# POWER2.net
KiCad netlist of a schematic drawn in Altium Designer
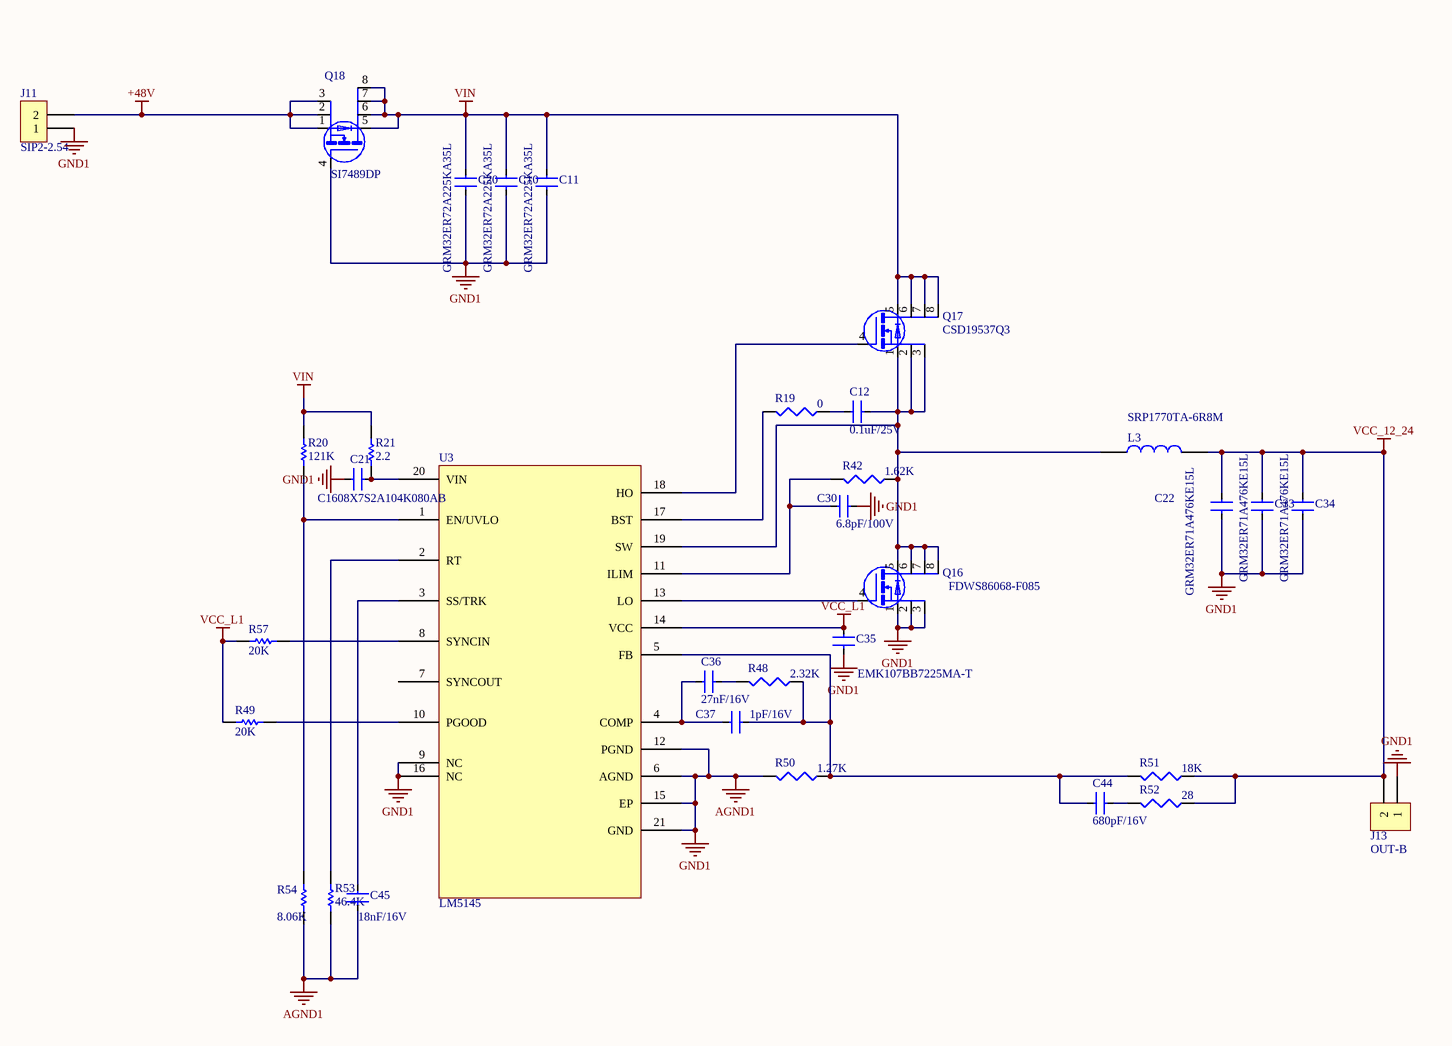
[diagram p0: POWER2.SchDoc]

(export (version "E")
  (design (tool "Eeschema 10.0.6"))
  (components
    (comp (ref "C10")
      (value "GRM32ER72A225KA35L")
      (footprint "1210C")
      (description "CCX85-103")
      (libsource (lib "无极性电容") (part "0.01UF"))
    )
    (comp (ref "C11")
      (value "GRM32ER72A225KA35L")
      (footprint "1210C")
      (description "CCX85-103")
      (libsource (lib "无极性电容") (part "0.01UF"))
    )
    (comp (ref "C12")
      (value "0.1uF/25V")
      (footprint "0603C")
      (description "CCX85-103")
      (libsource (lib "无极性电容") (part "0.01UF"))
    )
    (comp (ref "C20")
      (value "GRM32ER72A225KA35L")
      (footprint "1210C")
      (description "CCX85-103")
      (libsource (lib "无极性电容") (part "0.01UF"))
    )
    (comp (ref "C21")
      (value "C1608X7S2A104K080AB")
      (footprint "0603C")
      (description "CCX85-103")
      (libsource (lib "无极性电容") (part "0.01UF"))
    )
    (comp (ref "C22")
      (value "GRM32ER71A476KE15L")
      (footprint "1210C")
      (description "CCX85-103")
      (libsource (lib "无极性电容") (part "0.01UF"))
    )
    (comp (ref "C30")
      (value "6.8pF/100V")
      (footprint "0603C")
      (description "CCX85-103")
      (libsource (lib "无极性电容") (part "0.01UF"))
    )
    (comp (ref "C33")
      (value "GRM32ER71A476KE15L")
      (footprint "1210C")
      (description "CCX85-103")
      (libsource (lib "无极性电容") (part "0.01UF"))
    )
    (comp (ref "C34")
      (value "GRM32ER71A476KE15L")
      (footprint "1210C")
      (description "CCX85-103")
      (libsource (lib "无极性电容") (part "0.01UF"))
    )
    (comp (ref "C35")
      (value "EMK107BB7225MA-T")
      (footprint "0603C")
      (description "CCX85-103")
      (libsource (lib "无极性电容") (part "0.01UF"))
    )
    (comp (ref "C36")
      (value "27nF/16V")
      (footprint "0603C")
      (description "CCX85-103")
      (libsource (lib "无极性电容") (part "0.01UF"))
    )
    (comp (ref "C37")
      (value "1pF/16V")
      (footprint "0603C")
      (description "CCX85-103")
      (libsource (lib "无极性电容") (part "0.01UF"))
    )
    (comp (ref "C44")
      (value "680pF/16V")
      (footprint "0603C")
      (description "CCX85-103")
      (libsource (lib "无极性电容") (part "0.01UF"))
    )
    (comp (ref "C45")
      (value "18nF/16V")
      (footprint "0603C")
      (description "CCX85-103")
      (libsource (lib "无极性电容") (part "0.01UF"))
    )
    (comp (ref "J11")
      (value "SIP2-2.54")
      (footprint "CH3.96-2P")
      (description "CN-SIP2-2.54")
      (libsource (lib "接插件") (part "SIP2-2.54"))
    )
    (comp (ref "J13")
      (value "OUT-B")
      (footprint "CH3.96-2P")
      (description "Connector")
      (libsource (lib "SM") (part "CON2"))
    )
    (comp (ref "L3")
      (value "SRP1770TA-6R8M")
      (footprint "SRP1270-2R2M")
      (libsource (lib "*") (part "INDUCTOR"))
    )
    (comp (ref "Q16")
      (value "FDWS86068-F085")
      (footprint "PowerPAK SO-8")
      (description "Si4004DY")
      (libsource (lib "") (part "Si4004DY_1"))
    )
    (comp (ref "Q17")
      (value "CSD19537Q3")
      (footprint "PowerPAK SO-8")
      (description "Si4004DY")
      (libsource (lib "") (part "Si4004DY_1"))
    )
    (comp (ref "Q18")
      (value "SI7489DP")
      (footprint "PowerPAK SO-8")
      (description "Si4004DY")
      (libsource (lib "Schlib_20110825") (part "Si4004DY"))
    )
    (comp (ref "R19")
      (value "0")
      (footprint "0603R")
      (description "Resistor")
      (fields (field (name "PUBLISHER") "Altium Limited"))
      (libsource (lib "SM") (part "Res3"))
    )
    (comp (ref "R20")
      (value "121K")
      (footprint "0805R")
      (description "Semiconductor Resistor")
      (fields (field (name "PUBLISHER") "Altium Limited"))
      (libsource (lib "Miscellaneous Devices") (part "Res Semi"))
    )
    (comp (ref "R21")
      (value "2.2")
      (footprint "0603R")
      (description "Semiconductor Resistor")
      (fields (field (name "PUBLISHER") "Altium Limited"))
      (libsource (lib "Miscellaneous Devices") (part "Res Semi"))
    )
    (comp (ref "R42")
      (value "1.62K")
      (footprint "0603R")
      (description "Resistor")
      (fields (field (name "PUBLISHER") "Altium Limited"))
      (libsource (lib "SM") (part "Res3"))
    )
    (comp (ref "R48")
      (value "2.32K")
      (footprint "0603R")
      (description "Resistor")
      (fields (field (name "PUBLISHER") "Altium Limited"))
      (libsource (lib "SM") (part "Res3"))
    )
    (comp (ref "R49")
      (value "20K")
      (footprint "0603R")
      (description "Semiconductor Resistor")
      (fields (field (name "PUBLISHER") "Altium Limited"))
      (libsource (lib "Miscellaneous Devices") (part "Res Semi"))
    )
    (comp (ref "R50")
      (value "1.27K")
      (footprint "0603R")
      (description "Resistor")
      (fields (field (name "PUBLISHER") "Altium Limited"))
      (libsource (lib "SM") (part "Res3"))
    )
    (comp (ref "R51")
      (value "18K")
      (footprint "0603R")
      (description "Resistor")
      (fields (field (name "PUBLISHER") "Altium Limited"))
      (libsource (lib "SM") (part "Res3"))
    )
    (comp (ref "R52")
      (value "28")
      (footprint "0603R")
      (description "Resistor")
      (fields (field (name "PUBLISHER") "Altium Limited"))
      (libsource (lib "SM") (part "Res3"))
    )
    (comp (ref "R53")
      (value "46.4K")
      (footprint "0603R")
      (description "Semiconductor Resistor")
      (fields (field (name "PUBLISHER") "Altium Limited"))
      (libsource (lib "Miscellaneous Devices") (part "Res Semi"))
    )
    (comp (ref "R54")
      (value "8.06K")
      (footprint "0603R")
      (description "Semiconductor Resistor")
      (fields (field (name "PUBLISHER") "Altium Limited"))
      (libsource (lib "Miscellaneous Devices") (part "Res Semi"))
    )
    (comp (ref "R57")
      (value "20K")
      (footprint "0603R")
      (description "Semiconductor Resistor")
      (fields (field (name "PUBLISHER") "Altium Limited"))
      (libsource (lib "Miscellaneous Devices") (part "Res Semi"))
    )
    (comp (ref "U3")
      (value "LM5145")
      (footprint "QFN050P600-8N")
      (libsource (lib "Schlib_20110825") (part "LM5145"))
    )
  )
  (nets
    (net (code "1") (name "+48V") (class "Default")
      (node (ref "J11") (pin "2") (pinfunction "2_2") (pintype "passive"))
      (node (ref "Q18") (pin "1") (pinfunction "S_1") (pintype "passive"))
      (node (ref "Q18") (pin "2") (pinfunction "S_2") (pintype "passive"))
      (node (ref "Q18") (pin "3") (pinfunction "S_3") (pintype "passive"))
    )
    (net (code "2") (name "AGND1") (class "Default")
      (node (ref "C10") (pin "2") (pinfunction "2_2") (pintype "passive"))
      (node (ref "C11") (pin "2") (pinfunction "2_2") (pintype "passive"))
      (node (ref "C20") (pin "2") (pinfunction "2_2") (pintype "passive"))
      (node (ref "C21") (pin "1") (pinfunction "1_1") (pintype "passive"))
      (node (ref "C22") (pin "2") (pinfunction "2_2") (pintype "passive"))
      (node (ref "C30") (pin "1") (pinfunction "1_1") (pintype "passive"))
      (node (ref "C33") (pin "2") (pinfunction "2_2") (pintype "passive"))
      (node (ref "C34") (pin "2") (pinfunction "2_2") (pintype "passive"))
      (node (ref "C35") (pin "2") (pinfunction "2_2") (pintype "passive"))
      (node (ref "C45") (pin "2") (pinfunction "2_2") (pintype "passive"))
      (node (ref "J11") (pin "1") (pinfunction "1_1") (pintype "passive"))
      (node (ref "J13") (pin "1") (pinfunction "1_1") (pintype "passive"))
      (node (ref "Q16") (pin "1") (pinfunction "S_1") (pintype "passive"))
      (node (ref "Q16") (pin "2") (pinfunction "S_2") (pintype "passive"))
      (node (ref "Q16") (pin "3") (pinfunction "S_3") (pintype "passive"))
      (node (ref "Q18") (pin "4") (pinfunction "G_4") (pintype "passive"))
      (node (ref "R50") (pin "2") (pinfunction "2_2") (pintype "passive"))
      (node (ref "R53") (pin "1") (pinfunction "1_1") (pintype "passive"))
      (node (ref "R54") (pin "1") (pinfunction "1_1") (pintype "passive"))
      (node (ref "U3") (pin "12") (pinfunction "PGND_12") (pintype "passive"))
      (node (ref "U3") (pin "15") (pinfunction "EP_15") (pintype "passive"))
      (node (ref "U3") (pin "16") (pinfunction "NC_16") (pintype "passive"))
      (node (ref "U3") (pin "21") (pinfunction "GND_21") (pintype "passive"))
      (node (ref "U3") (pin "6") (pinfunction "AGND_6") (pintype "passive"))
      (node (ref "U3") (pin "9") (pinfunction "NC_9") (pintype "passive"))
    )
    (net (code "3") (name "Net-(C12-Pad1)") (class "Default")
      (node (ref "C12") (pin "1") (pinfunction "1_1") (pintype "passive"))
      (node (ref "R19") (pin "1") (pinfunction "1_1") (pintype "passive"))
    )
    (net (code "4") (name "Net-(C36-Pad2)") (class "Default")
      (node (ref "C36") (pin "2") (pinfunction "2_2") (pintype "passive"))
      (node (ref "R48") (pin "2") (pinfunction "2_2") (pintype "passive"))
    )
    (net (code "5") (name "Net-(C44-Pad2)") (class "Default")
      (node (ref "C44") (pin "2") (pinfunction "2_2") (pintype "passive"))
      (node (ref "R52") (pin "2") (pinfunction "2_2") (pintype "passive"))
    )
    (net (code "6") (name "Net-(Q16-G)") (class "Default")
      (node (ref "Q16") (pin "4") (pinfunction "G_4") (pintype "passive"))
      (node (ref "U3") (pin "13") (pinfunction "LO_13") (pintype "passive"))
    )
    (net (code "7") (name "Net-(Q17-G)") (class "Default")
      (node (ref "Q17") (pin "4") (pinfunction "G_4") (pintype "passive"))
      (node (ref "U3") (pin "18") (pinfunction "HO_18") (pintype "passive"))
    )
    (net (code "8") (name "Net-(U3-BST)") (class "Default")
      (node (ref "R19") (pin "2") (pinfunction "2_2") (pintype "passive"))
      (node (ref "U3") (pin "17") (pinfunction "BST_17") (pintype "passive"))
    )
    (net (code "9") (name "Net-(U3-COMP)") (class "Default")
      (node (ref "C36") (pin "1") (pinfunction "1_1") (pintype "passive"))
      (node (ref "C37") (pin "1") (pinfunction "1_1") (pintype "passive"))
      (node (ref "U3") (pin "4") (pinfunction "COMP_4") (pintype "passive"))
    )
    (net (code "10") (name "Net-(U3-EN{slash}UVLO)") (class "Default")
      (node (ref "R20") (pin "1") (pinfunction "1_1") (pintype "passive"))
      (node (ref "R54") (pin "2") (pinfunction "2_2") (pintype "passive"))
      (node (ref "U3") (pin "1") (pinfunction "EN/UVLO_1") (pintype "passive"))
    )
    (net (code "11") (name "Net-(U3-FB)") (class "Default")
      (node (ref "C37") (pin "2") (pinfunction "2_2") (pintype "passive"))
      (node (ref "C44") (pin "1") (pinfunction "1_1") (pintype "passive"))
      (node (ref "R48") (pin "1") (pinfunction "1_1") (pintype "passive"))
      (node (ref "R50") (pin "1") (pinfunction "1_1") (pintype "passive"))
      (node (ref "R51") (pin "2") (pinfunction "2_2") (pintype "passive"))
      (node (ref "U3") (pin "5") (pinfunction "FB_5") (pintype "passive"))
    )
    (net (code "12") (name "Net-(U3-ILIM)") (class "Default")
      (node (ref "C30") (pin "2") (pinfunction "2_2") (pintype "passive"))
      (node (ref "R42") (pin "2") (pinfunction "2_2") (pintype "passive"))
      (node (ref "U3") (pin "11") (pinfunction "ILIM_11") (pintype "passive"))
    )
    (net (code "13") (name "Net-(U3-PGOOD)") (class "Default")
      (node (ref "R49") (pin "1") (pinfunction "1_1") (pintype "passive"))
      (node (ref "U3") (pin "10") (pinfunction "PGOOD_10") (pintype "passive"))
    )
    (net (code "14") (name "Net-(U3-RT)") (class "Default")
      (node (ref "R53") (pin "2") (pinfunction "2_2") (pintype "passive"))
      (node (ref "U3") (pin "2") (pinfunction "RT_2") (pintype "passive"))
    )
    (net (code "15") (name "Net-(U3-SS{slash}TRK)") (class "Default")
      (node (ref "C45") (pin "1") (pinfunction "1_1") (pintype "passive"))
      (node (ref "U3") (pin "3") (pinfunction "SS/TRK_3") (pintype "passive"))
    )
    (net (code "16") (name "Net-(U3-SW)") (class "Default")
      (node (ref "C12") (pin "2") (pinfunction "2_2") (pintype "passive"))
      (node (ref "L3") (pin "1") (pinfunction "1_1") (pintype "passive"))
      (node (ref "Q16") (pin "5") (pinfunction "D_5") (pintype "passive"))
      (node (ref "Q16") (pin "6") (pinfunction "D_6") (pintype "passive"))
      (node (ref "Q16") (pin "7") (pinfunction "D_7") (pintype "passive"))
      (node (ref "Q16") (pin "8") (pinfunction "D_8") (pintype "passive"))
      (node (ref "Q17") (pin "1") (pinfunction "S_1") (pintype "passive"))
      (node (ref "Q17") (pin "2") (pinfunction "S_2") (pintype "passive"))
      (node (ref "Q17") (pin "3") (pinfunction "S_3") (pintype "passive"))
      (node (ref "R42") (pin "1") (pinfunction "1_1") (pintype "passive"))
      (node (ref "U3") (pin "19") (pinfunction "SW_19") (pintype "passive"))
    )
    (net (code "17") (name "Net-(U3-SYNCIN)") (class "Default")
      (node (ref "R57") (pin "1") (pinfunction "1_1") (pintype "passive"))
      (node (ref "U3") (pin "8") (pinfunction "SYNCIN_8") (pintype "passive"))
    )
    (net (code "18") (name "Net-(U3-VIN)") (class "Default")
      (node (ref "C21") (pin "2") (pinfunction "2_2") (pintype "passive"))
      (node (ref "R21") (pin "2") (pinfunction "2_2") (pintype "passive"))
      (node (ref "U3") (pin "20") (pinfunction "VIN_20") (pintype "passive"))
    )
    (net (code "19") (name "VCC_12_24") (class "Default")
      (node (ref "C22") (pin "1") (pinfunction "1_1") (pintype "passive"))
      (node (ref "C33") (pin "1") (pinfunction "1_1") (pintype "passive"))
      (node (ref "C34") (pin "1") (pinfunction "1_1") (pintype "passive"))
      (node (ref "J13") (pin "2") (pinfunction "2_2") (pintype "passive"))
      (node (ref "L3") (pin "2") (pinfunction "2_2") (pintype "passive"))
      (node (ref "R51") (pin "1") (pinfunction "1_1") (pintype "passive"))
      (node (ref "R52") (pin "1") (pinfunction "1_1") (pintype "passive"))
    )
    (net (code "20") (name "VCC_L1") (class "Default")
      (node (ref "C35") (pin "1") (pinfunction "1_1") (pintype "passive"))
      (node (ref "R49") (pin "2") (pinfunction "2_2") (pintype "passive"))
      (node (ref "R57") (pin "2") (pinfunction "2_2") (pintype "passive"))
      (node (ref "U3") (pin "14") (pinfunction "VCC_14") (pintype "passive"))
    )
    (net (code "21") (name "VIN") (class "Default")
      (node (ref "C10") (pin "1") (pinfunction "1_1") (pintype "passive"))
      (node (ref "C11") (pin "1") (pinfunction "1_1") (pintype "passive"))
      (node (ref "C20") (pin "1") (pinfunction "1_1") (pintype "passive"))
      (node (ref "Q17") (pin "5") (pinfunction "D_5") (pintype "passive"))
      (node (ref "Q17") (pin "6") (pinfunction "D_6") (pintype "passive"))
      (node (ref "Q17") (pin "7") (pinfunction "D_7") (pintype "passive"))
      (node (ref "Q17") (pin "8") (pinfunction "D_8") (pintype "passive"))
      (node (ref "Q18") (pin "5") (pinfunction "D_5") (pintype "passive"))
      (node (ref "Q18") (pin "6") (pinfunction "D_6") (pintype "passive"))
      (node (ref "Q18") (pin "7") (pinfunction "D_7") (pintype "passive"))
      (node (ref "Q18") (pin "8") (pinfunction "D_8") (pintype "passive"))
      (node (ref "R20") (pin "2") (pinfunction "2_2") (pintype "passive"))
      (node (ref "R21") (pin "1") (pinfunction "1_1") (pintype "passive"))
    )
    (net (code "22") (name "unconnected-(U3-SYNCOUT-Pad7)") (class "Default")
      (node (ref "U3") (pin "7") (pinfunction "SYNCOUT_7") (pintype "passive"))
    )
  )
)
